# health_companion.net
KiCad netlist of a schematic drawn in EAGLE
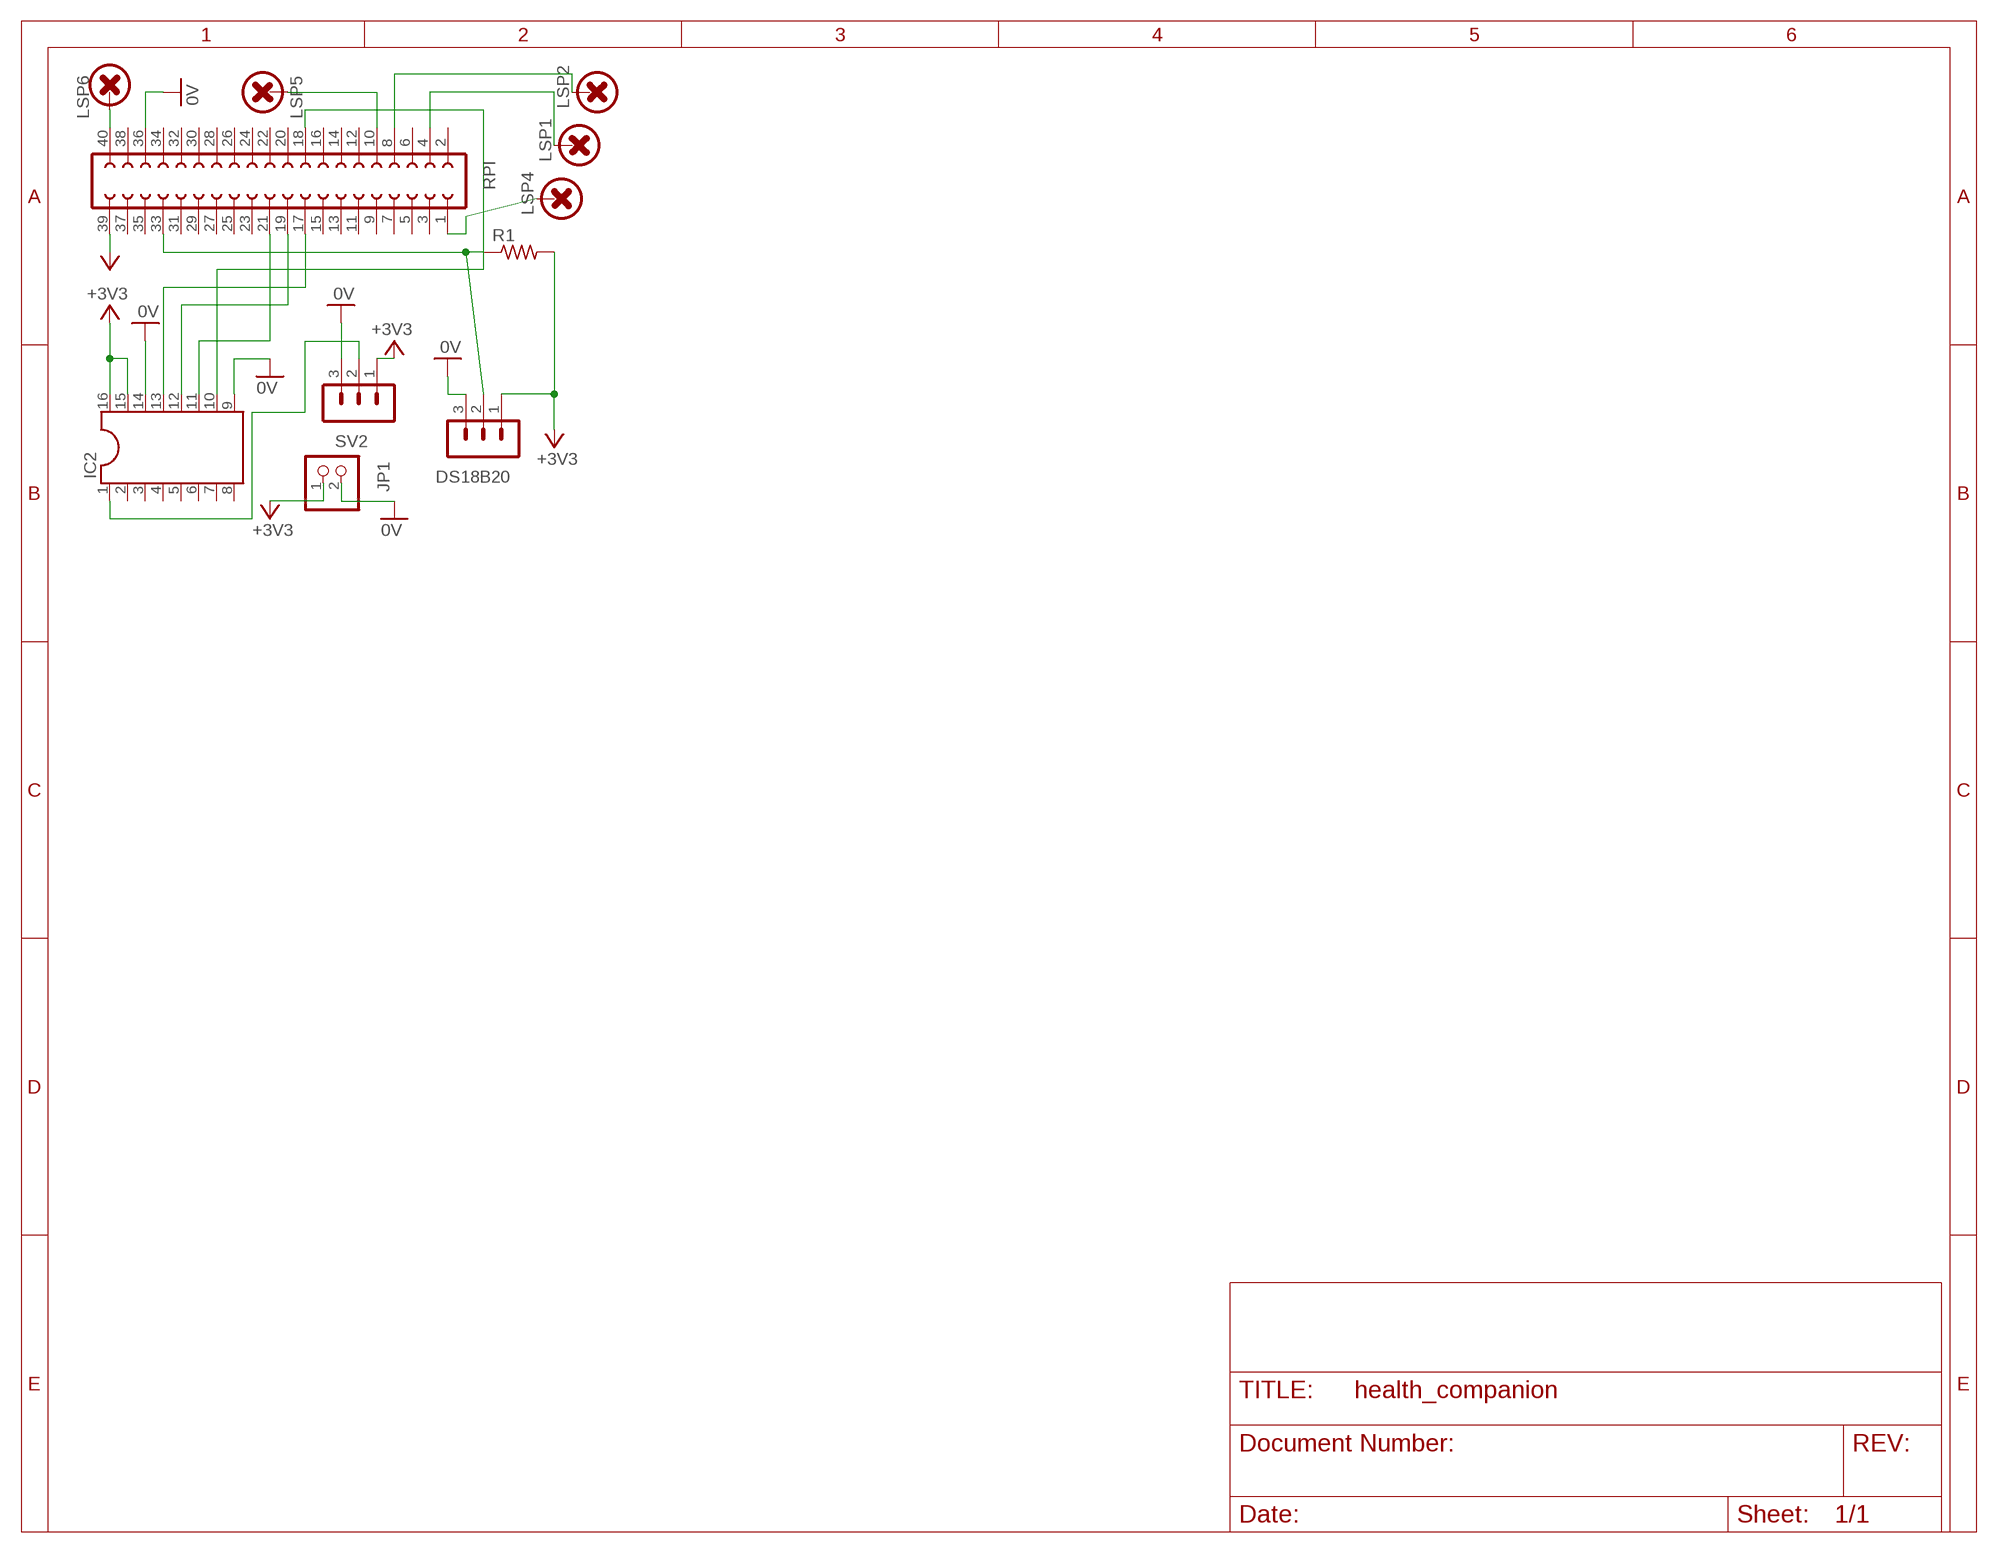
[diagram p0: schematic, sheet 1]

(export (version "E")
  (design (tool "Eeschema 10.0.6"))
  (components
    (comp (ref "DS18B20")
      (value "MA03-1")
      (footprint "eagle-import:MA03-1")
      (libsource (lib "eagle-import") (part "MA03-1"))
    )
    (comp (ref "IC2")
      (value "DIL16")
      (footprint "eagle-import:DIL16")
      (libsource (lib "eagle-import") (part "DIL16"))
    )
    (comp (ref "JP1")
      (value "PINHD-1X2")
      (footprint "eagle-import:1X02")
      (libsource (lib "eagle-import") (part "PINHD-1X2"))
    )
    (comp (ref "LSP1")
      (value "LSP11-VAR12.8MM")
      (footprint "eagle-import:LSP11")
      (libsource (lib "eagle-import") (part "LSP11-VAR12.8MM"))
    )
    (comp (ref "LSP2")
      (value "LSP11-VAR12.8MM")
      (footprint "eagle-import:LSP11")
      (libsource (lib "eagle-import") (part "LSP11-VAR12.8MM"))
    )
    (comp (ref "LSP4")
      (value "LSP11-VAR12.8MM")
      (footprint "eagle-import:LSP11")
      (libsource (lib "eagle-import") (part "LSP11-VAR12.8MM"))
    )
    (comp (ref "LSP5")
      (value "LSP11-VAR12.8MM")
      (footprint "eagle-import:LSP11")
      (libsource (lib "eagle-import") (part "LSP11-VAR12.8MM"))
    )
    (comp (ref "LSP6")
      (value "LSP11-VAR12.8MM")
      (footprint "eagle-import:LSP11")
      (libsource (lib "eagle-import") (part "LSP11-VAR12.8MM"))
    )
    (comp (ref "R1")
      (value "R-US_0204/5")
      (footprint "eagle-import:0204_5")
      (libsource (lib "eagle-import") (part "R-US_0204/5"))
    )
    (comp (ref "RPI")
      (value "FE20-2")
      (footprint "eagle-import:FE20-2")
      (libsource (lib "eagle-import") (part "FE20-2"))
    )
    (comp (ref "SV2")
      (value "MA03-1")
      (footprint "eagle-import:MA03-1")
      (libsource (lib "eagle-import") (part "MA03-1"))
    )
  )
  (nets
    (net (code "1") (name "+3V3") (class "Default")
      (node (ref "DS18B20") (pin "1") (pinfunction "1_1") (pintype "passive"))
      (node (ref "IC2") (pin "15") (pinfunction "15_15") (pintype "passive"))
      (node (ref "IC2") (pin "16") (pinfunction "16_16") (pintype "passive"))
      (node (ref "JP1") (pin "1") (pinfunction "1_1") (pintype "passive"))
      (node (ref "R1") (pin "2") (pinfunction "2_2") (pintype "passive"))
      (node (ref "RPI") (pin "39") (pinfunction "39_39") (pintype "passive"))
      (node (ref "SV2") (pin "1") (pinfunction "1_1") (pintype "passive"))
    )
    (net (code "2") (name "0V") (class "Default")
      (node (ref "DS18B20") (pin "3") (pinfunction "3_3") (pintype "passive"))
      (node (ref "IC2") (pin "14") (pinfunction "14_14") (pintype "passive"))
      (node (ref "IC2") (pin "9") (pinfunction "9_9") (pintype "passive"))
      (node (ref "JP1") (pin "2") (pinfunction "2_2") (pintype "passive"))
      (node (ref "RPI") (pin "36") (pinfunction "36_36") (pintype "passive"))
      (node (ref "SV2") (pin "3") (pinfunction "3_3") (pintype "passive"))
    )
    (net (code "3") (name "Net-(DS18B20-Pad2)") (class "Default")
      (node (ref "DS18B20") (pin "2") (pinfunction "2_2") (pintype "passive"))
      (node (ref "R1") (pin "1") (pinfunction "1_1") (pintype "passive"))
      (node (ref "RPI") (pin "33") (pinfunction "33_33") (pintype "passive"))
    )
    (net (code "4") (name "Net-(IC2-Pad1)") (class "Default")
      (node (ref "IC2") (pin "1") (pinfunction "1_1") (pintype "passive"))
      (node (ref "SV2") (pin "2") (pinfunction "2_2") (pintype "passive"))
    )
    (net (code "5") (name "Net-(IC2-Pad10)") (class "Default")
      (node (ref "IC2") (pin "10") (pinfunction "10_10") (pintype "passive"))
      (node (ref "RPI") (pin "18") (pinfunction "18_18") (pintype "passive"))
    )
    (net (code "6") (name "Net-(IC2-Pad11)") (class "Default")
      (node (ref "IC2") (pin "11") (pinfunction "11_11") (pintype "passive"))
      (node (ref "RPI") (pin "21") (pinfunction "21_21") (pintype "passive"))
    )
    (net (code "7") (name "Net-(IC2-Pad12)") (class "Default")
      (node (ref "IC2") (pin "12") (pinfunction "12_12") (pintype "passive"))
      (node (ref "RPI") (pin "19") (pinfunction "19_19") (pintype "passive"))
    )
    (net (code "8") (name "Net-(IC2-Pad13)") (class "Default")
      (node (ref "IC2") (pin "13") (pinfunction "13_13") (pintype "passive"))
      (node (ref "RPI") (pin "17") (pinfunction "17_17") (pintype "passive"))
    )
    (net (code "9") (name "Net-(LSP1-PadMP)") (class "Default")
      (node (ref "LSP1") (pin "MP") (pinfunction "MP_MP") (pintype "passive"))
      (node (ref "RPI") (pin "4") (pinfunction "4_4") (pintype "passive"))
    )
    (net (code "10") (name "Net-(LSP2-PadMP)") (class "Default")
      (node (ref "LSP2") (pin "MP") (pinfunction "MP_MP") (pintype "passive"))
      (node (ref "RPI") (pin "8") (pinfunction "8_8") (pintype "passive"))
    )
    (net (code "11") (name "Net-(LSP4-PadMP)") (class "Default")
      (node (ref "LSP4") (pin "MP") (pinfunction "MP_MP") (pintype "passive"))
      (node (ref "RPI") (pin "1") (pinfunction "1_1") (pintype "passive"))
    )
    (net (code "12") (name "Net-(LSP5-PadMP)") (class "Default")
      (node (ref "LSP5") (pin "MP") (pinfunction "MP_MP") (pintype "passive"))
      (node (ref "RPI") (pin "10") (pinfunction "10_10") (pintype "passive"))
    )
    (net (code "13") (name "Net-(LSP6-PadMP)") (class "Default")
      (node (ref "LSP6") (pin "MP") (pinfunction "MP_MP") (pintype "passive"))
      (node (ref "RPI") (pin "40") (pinfunction "40_40") (pintype "passive"))
    )
    (net (code "14") (name "unconnected-(IC2-Pad2)") (class "Default")
      (node (ref "IC2") (pin "2") (pinfunction "2_2") (pintype "passive"))
    )
    (net (code "15") (name "unconnected-(IC2-Pad3)") (class "Default")
      (node (ref "IC2") (pin "3") (pinfunction "3_3") (pintype "passive"))
    )
    (net (code "16") (name "unconnected-(IC2-Pad4)") (class "Default")
      (node (ref "IC2") (pin "4") (pinfunction "4_4") (pintype "passive"))
    )
    (net (code "17") (name "unconnected-(IC2-Pad5)") (class "Default")
      (node (ref "IC2") (pin "5") (pinfunction "5_5") (pintype "passive"))
    )
    (net (code "18") (name "unconnected-(IC2-Pad6)") (class "Default")
      (node (ref "IC2") (pin "6") (pinfunction "6_6") (pintype "passive"))
    )
    (net (code "19") (name "unconnected-(IC2-Pad7)") (class "Default")
      (node (ref "IC2") (pin "7") (pinfunction "7_7") (pintype "passive"))
    )
    (net (code "20") (name "unconnected-(IC2-Pad8)") (class "Default")
      (node (ref "IC2") (pin "8") (pinfunction "8_8") (pintype "passive"))
    )
    (net (code "21") (name "unconnected-(RPI-Pad2)") (class "Default")
      (node (ref "RPI") (pin "2") (pinfunction "2_2") (pintype "passive"))
    )
    (net (code "22") (name "unconnected-(RPI-Pad3)") (class "Default")
      (node (ref "RPI") (pin "3") (pinfunction "3_3") (pintype "passive"))
    )
    (net (code "23") (name "unconnected-(RPI-Pad5)") (class "Default")
      (node (ref "RPI") (pin "5") (pinfunction "5_5") (pintype "passive"))
    )
    (net (code "24") (name "unconnected-(RPI-Pad6)") (class "Default")
      (node (ref "RPI") (pin "6") (pinfunction "6_6") (pintype "passive"))
    )
    (net (code "25") (name "unconnected-(RPI-Pad7)") (class "Default")
      (node (ref "RPI") (pin "7") (pinfunction "7_7") (pintype "passive"))
    )
    (net (code "26") (name "unconnected-(RPI-Pad9)") (class "Default")
      (node (ref "RPI") (pin "9") (pinfunction "9_9") (pintype "passive"))
    )
    (net (code "27") (name "unconnected-(RPI-Pad11)") (class "Default")
      (node (ref "RPI") (pin "11") (pinfunction "11_11") (pintype "passive"))
    )
    (net (code "28") (name "unconnected-(RPI-Pad12)") (class "Default")
      (node (ref "RPI") (pin "12") (pinfunction "12_12") (pintype "passive"))
    )
    (net (code "29") (name "unconnected-(RPI-Pad13)") (class "Default")
      (node (ref "RPI") (pin "13") (pinfunction "13_13") (pintype "passive"))
    )
    (net (code "30") (name "unconnected-(RPI-Pad14)") (class "Default")
      (node (ref "RPI") (pin "14") (pinfunction "14_14") (pintype "passive"))
    )
    (net (code "31") (name "unconnected-(RPI-Pad15)") (class "Default")
      (node (ref "RPI") (pin "15") (pinfunction "15_15") (pintype "passive"))
    )
    (net (code "32") (name "unconnected-(RPI-Pad16)") (class "Default")
      (node (ref "RPI") (pin "16") (pinfunction "16_16") (pintype "passive"))
    )
    (net (code "33") (name "unconnected-(RPI-Pad20)") (class "Default")
      (node (ref "RPI") (pin "20") (pinfunction "20_20") (pintype "passive"))
    )
    (net (code "34") (name "unconnected-(RPI-Pad22)") (class "Default")
      (node (ref "RPI") (pin "22") (pinfunction "22_22") (pintype "passive"))
    )
    (net (code "35") (name "unconnected-(RPI-Pad23)") (class "Default")
      (node (ref "RPI") (pin "23") (pinfunction "23_23") (pintype "passive"))
    )
    (net (code "36") (name "unconnected-(RPI-Pad24)") (class "Default")
      (node (ref "RPI") (pin "24") (pinfunction "24_24") (pintype "passive"))
    )
    (net (code "37") (name "unconnected-(RPI-Pad25)") (class "Default")
      (node (ref "RPI") (pin "25") (pinfunction "25_25") (pintype "passive"))
    )
    (net (code "38") (name "unconnected-(RPI-Pad26)") (class "Default")
      (node (ref "RPI") (pin "26") (pinfunction "26_26") (pintype "passive"))
    )
    (net (code "39") (name "unconnected-(RPI-Pad27)") (class "Default")
      (node (ref "RPI") (pin "27") (pinfunction "27_27") (pintype "passive"))
    )
    (net (code "40") (name "unconnected-(RPI-Pad28)") (class "Default")
      (node (ref "RPI") (pin "28") (pinfunction "28_28") (pintype "passive"))
    )
    (net (code "41") (name "unconnected-(RPI-Pad29)") (class "Default")
      (node (ref "RPI") (pin "29") (pinfunction "29_29") (pintype "passive"))
    )
    (net (code "42") (name "unconnected-(RPI-Pad30)") (class "Default")
      (node (ref "RPI") (pin "30") (pinfunction "30_30") (pintype "passive"))
    )
    (net (code "43") (name "unconnected-(RPI-Pad31)") (class "Default")
      (node (ref "RPI") (pin "31") (pinfunction "31_31") (pintype "passive"))
    )
    (net (code "44") (name "unconnected-(RPI-Pad32)") (class "Default")
      (node (ref "RPI") (pin "32") (pinfunction "32_32") (pintype "passive"))
    )
    (net (code "45") (name "unconnected-(RPI-Pad34)") (class "Default")
      (node (ref "RPI") (pin "34") (pinfunction "34_34") (pintype "passive"))
    )
    (net (code "46") (name "unconnected-(RPI-Pad35)") (class "Default")
      (node (ref "RPI") (pin "35") (pinfunction "35_35") (pintype "passive"))
    )
    (net (code "47") (name "unconnected-(RPI-Pad37)") (class "Default")
      (node (ref "RPI") (pin "37") (pinfunction "37_37") (pintype "passive"))
    )
    (net (code "48") (name "unconnected-(RPI-Pad38)") (class "Default")
      (node (ref "RPI") (pin "38") (pinfunction "38_38") (pintype "passive"))
    )
  )
)
